# Si4825_KIT_SMT.net
KiCad netlist of a schematic drawn in EAGLE
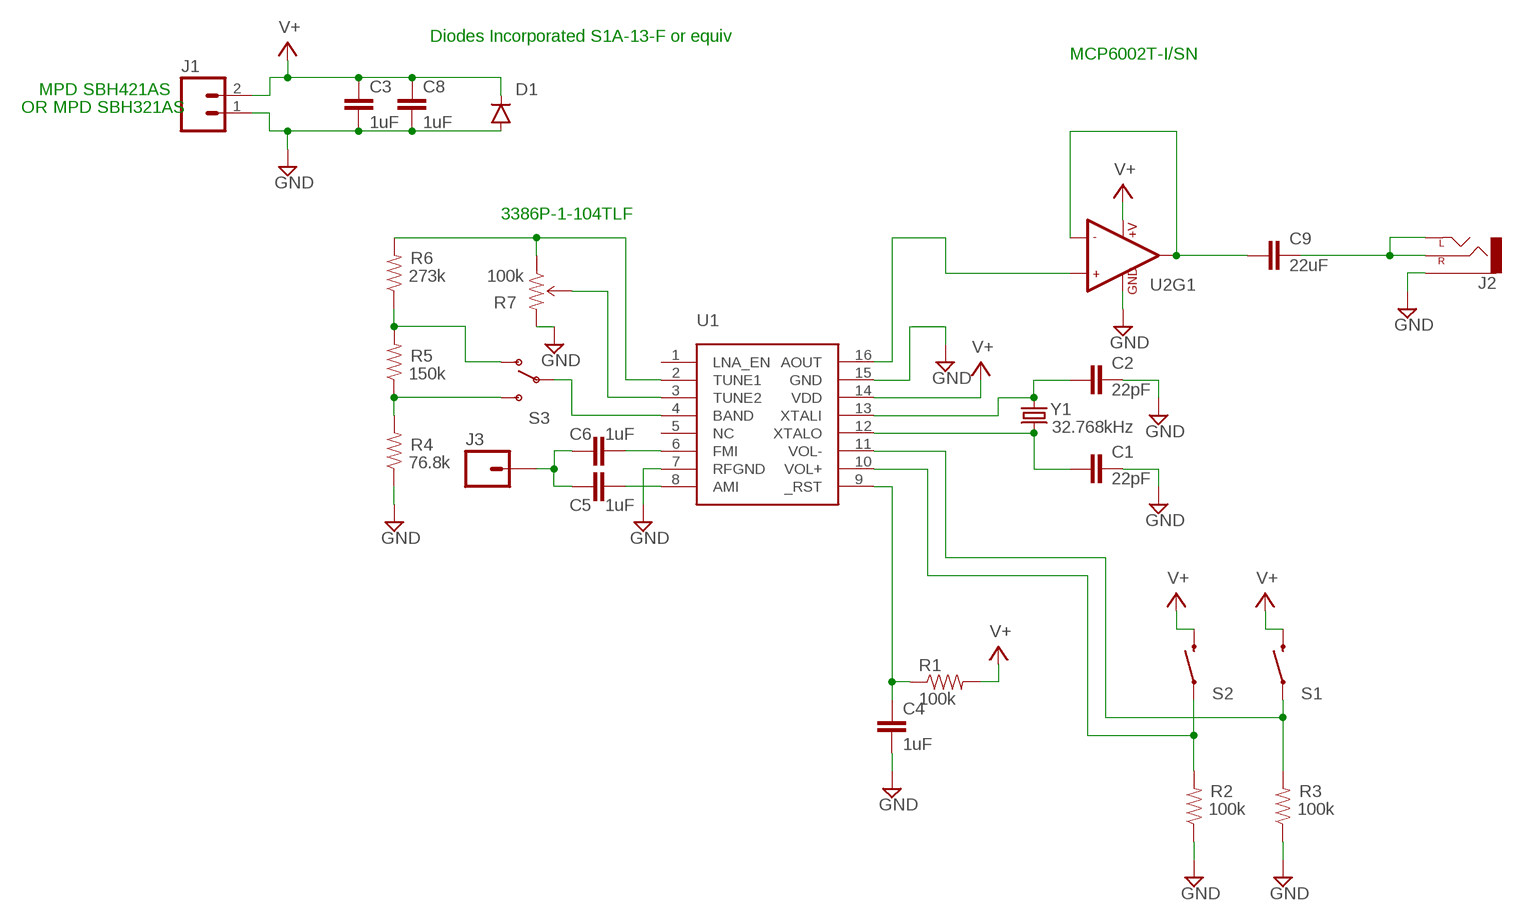
[diagram p0: schematic, sheet 1]

(export (version "E")
  (design (tool "Eeschema 10.0.6"))
  (components
    (comp (ref "C1")
      (value "22pF")
      (footprint "eagle-import:0805")
      (libsource (lib "eagle-import") (part "CAP0805"))
    )
    (comp (ref "C2")
      (value "22pF")
      (footprint "eagle-import:0805")
      (libsource (lib "eagle-import") (part "CAP0805"))
    )
    (comp (ref "C3")
      (value "1uF")
      (footprint "eagle-import:0805")
      (libsource (lib "eagle-import") (part "CAP0805"))
    )
    (comp (ref "C4")
      (value "1uF")
      (footprint "eagle-import:0805")
      (libsource (lib "eagle-import") (part "CAP0805"))
    )
    (comp (ref "C5")
      (value "1uF")
      (footprint "eagle-import:0805")
      (libsource (lib "eagle-import") (part "CAP0805"))
    )
    (comp (ref "C6")
      (value "1uF")
      (footprint "eagle-import:0805")
      (libsource (lib "eagle-import") (part "CAP0805"))
    )
    (comp (ref "C8")
      (value "1uF")
      (footprint "eagle-import:0805")
      (libsource (lib "eagle-import") (part "CAP0805"))
    )
    (comp (ref "C9")
      (value "22uF")
      (footprint "eagle-import:0805")
      (libsource (lib "eagle-import") (part "CAP0805"))
    )
    (comp (ref "D1")
      (value "DIODESMA")
      (footprint "eagle-import:SMA-DIODE")
      (libsource (lib "eagle-import") (part "DIODESMA"))
    )
    (comp (ref "J1")
      (value "M02PTH")
      (footprint "eagle-import:1X02")
      (libsource (lib "eagle-import") (part "M02PTH"))
    )
    (comp (ref "J2")
      (value "AUDIO-JACKPTH")
      (footprint "eagle-import:AUDIO-JACK")
      (libsource (lib "eagle-import") (part "AUDIO-JACKPTH"))
    )
    (comp (ref "J3")
      (value "M01PTH")
      (footprint "eagle-import:1X01")
      (libsource (lib "eagle-import") (part "M01PTH"))
    )
    (comp (ref "R1")
      (value "100k")
      (footprint "eagle-import:0805")
      (libsource (lib "eagle-import") (part "RESISTOR0805-RES"))
    )
    (comp (ref "R2")
      (value "100k")
      (footprint "eagle-import:0805")
      (libsource (lib "eagle-import") (part "RESISTOR0805-RES"))
    )
    (comp (ref "R3")
      (value "100k")
      (footprint "eagle-import:0805")
      (libsource (lib "eagle-import") (part "RESISTOR0805-RES"))
    )
    (comp (ref "R4")
      (value "76.8k")
      (footprint "eagle-import:0805")
      (libsource (lib "eagle-import") (part "RESISTOR0805-RES"))
    )
    (comp (ref "R5")
      (value "150k")
      (footprint "eagle-import:0805")
      (libsource (lib "eagle-import") (part "RESISTOR0805-RES"))
    )
    (comp (ref "R6")
      (value "273k")
      (footprint "eagle-import:0805")
      (libsource (lib "eagle-import") (part "RESISTOR0805-RES"))
    )
    (comp (ref "R7")
      (value "100k")
      (footprint "eagle-import:BOURNS_3386P")
      (libsource (lib "eagle-import") (part "BOURNS_3386P"))
    )
    (comp (ref "S1")
      (value "SWITCH-MOMENTARY-2PTH")
      (footprint "eagle-import:TACTILE-PTH")
      (libsource (lib "eagle-import") (part "SWITCH-MOMENTARY-2PTH"))
    )
    (comp (ref "S2")
      (value "SWITCH-MOMENTARY-2PTH")
      (footprint "eagle-import:TACTILE-PTH")
      (libsource (lib "eagle-import") (part "SWITCH-MOMENTARY-2PTH"))
    )
    (comp (ref "S3")
      (value "SWITCH-SPDTPTH")
      (footprint "eagle-import:SWITCH-SPDT")
      (libsource (lib "eagle-import") (part "SWITCH-SPDTPTH"))
    )
    (comp (ref "U1")
      (value "SI4825")
      (footprint "eagle-import:SO16")
      (libsource (lib "eagle-import") (part "SI4825"))
    )
    (comp (ref "U2")
      (value "LMV358SOIC")
      (footprint "eagle-import:SO08")
      (libsource (lib "eagle-import") (part "LMV358SOIC"))
    )
    (comp (ref "Y1")
      (value "32.768kHz")
      (footprint "eagle-import:TC26H")
      (libsource (lib "eagle-import") (part "CRYSTALTC26H"))
    )
  )
  (nets
    (net (code "1") (name "GND") (class "Default")
      (node (ref "C1") (pin "2") (pinfunction "2_2") (pintype "passive"))
      (node (ref "C2") (pin "2") (pinfunction "2_2") (pintype "passive"))
      (node (ref "C3") (pin "2") (pinfunction "2_2") (pintype "passive"))
      (node (ref "C4") (pin "2") (pinfunction "2_2") (pintype "passive"))
      (node (ref "C8") (pin "2") (pinfunction "2_2") (pintype "passive"))
      (node (ref "D1") (pin "A") (pinfunction "A_A") (pintype "passive"))
      (node (ref "J1") (pin "1") (pinfunction "1_1") (pintype "passive"))
      (node (ref "J2") (pin "SLEEVE") (pinfunction "SLEEVE_SLEEVE") (pintype "bidirectional"))
      (node (ref "R2") (pin "1") (pinfunction "1_1") (pintype "passive"))
      (node (ref "R3") (pin "1") (pinfunction "1_1") (pintype "passive"))
      (node (ref "R4") (pin "1") (pinfunction "1_1") (pintype "passive"))
      (node (ref "R7") (pin "P$3") (pinfunction "CW_P$3") (pintype "passive"))
      (node (ref "U1") (pin "15") (pinfunction "GND_15") (pintype "bidirectional"))
      (node (ref "U1") (pin "7") (pinfunction "RFGND_7") (pintype "bidirectional"))
      (node (ref "U2") (pin "4") (pinfunction "GND_4") (pintype "power_in"))
    )
    (net (code "2") (name "Net-(C5-Pad1)") (class "Default")
      (node (ref "C5") (pin "1") (pinfunction "1_1") (pintype "passive"))
      (node (ref "C6") (pin "1") (pinfunction "1_1") (pintype "passive"))
      (node (ref "J3") (pin "1") (pinfunction "1_1") (pintype "passive"))
    )
    (net (code "3") (name "Net-(J2-LEFT)") (class "Default")
      (node (ref "C9") (pin "2") (pinfunction "2_2") (pintype "passive"))
      (node (ref "J2") (pin "RING") (pinfunction "RIGHT_RING") (pintype "bidirectional"))
      (node (ref "J2") (pin "TIP") (pinfunction "LEFT_TIP") (pintype "bidirectional"))
    )
    (net (code "4") (name "Net-(R7-CCW)") (class "Default")
      (node (ref "R6") (pin "2") (pinfunction "2_2") (pintype "passive"))
      (node (ref "R7") (pin "P$1") (pinfunction "CCW_P$1") (pintype "passive"))
      (node (ref "U1") (pin "2") (pinfunction "TUNE1_2") (pintype "bidirectional"))
    )
    (net (code "5") (name "Net-(R7-WIPER)") (class "Default")
      (node (ref "R7") (pin "P$2") (pinfunction "WIPER_P$2") (pintype "passive"))
      (node (ref "U1") (pin "3") (pinfunction "TUNE2_3") (pintype "bidirectional"))
    )
    (net (code "6") (name "Net-(S3-O)") (class "Default")
      (node (ref "R5") (pin "2") (pinfunction "2_2") (pintype "passive"))
      (node (ref "R6") (pin "1") (pinfunction "1_1") (pintype "passive"))
      (node (ref "S3") (pin "1") (pinfunction "O_1") (pintype "passive"))
    )
    (net (code "7") (name "Net-(S3-P)") (class "Default")
      (node (ref "S3") (pin "2") (pinfunction "P_2") (pintype "passive"))
      (node (ref "U1") (pin "4") (pinfunction "BAND_4") (pintype "bidirectional"))
    )
    (net (code "8") (name "Net-(S3-S)") (class "Default")
      (node (ref "R4") (pin "2") (pinfunction "2_2") (pintype "passive"))
      (node (ref "R5") (pin "1") (pinfunction "1_1") (pintype "passive"))
      (node (ref "S3") (pin "3") (pinfunction "S_3") (pintype "passive"))
    )
    (net (code "9") (name "Net-(U1-AMI)") (class "Default")
      (node (ref "C5") (pin "2") (pinfunction "2_2") (pintype "passive"))
      (node (ref "U1") (pin "8") (pinfunction "AMI_8") (pintype "bidirectional"))
    )
    (net (code "10") (name "Net-(U1-AOUT)") (class "Default")
      (node (ref "U1") (pin "16") (pinfunction "AOUT_16") (pintype "bidirectional"))
      (node (ref "U2") (pin "3") (pinfunction "+IN1_3") (pintype "input"))
    )
    (net (code "11") (name "Net-(U1-FMI)") (class "Default")
      (node (ref "C6") (pin "2") (pinfunction "2_2") (pintype "passive"))
      (node (ref "U1") (pin "6") (pinfunction "FMI_6") (pintype "bidirectional"))
    )
    (net (code "12") (name "Net-(U1-VOL+)") (class "Default")
      (node (ref "R2") (pin "2") (pinfunction "2_2") (pintype "passive"))
      (node (ref "S2") (pin "1") (pinfunction "1_1") (pintype "passive"))
      (node (ref "U1") (pin "10") (pinfunction "VOL+_10") (pintype "bidirectional"))
    )
    (net (code "13") (name "Net-(U1-VOL-)") (class "Default")
      (node (ref "R3") (pin "2") (pinfunction "2_2") (pintype "passive"))
      (node (ref "S1") (pin "1") (pinfunction "1_1") (pintype "passive"))
      (node (ref "U1") (pin "11") (pinfunction "VOL-_11") (pintype "bidirectional"))
    )
    (net (code "14") (name "Net-(U1-XTALI)") (class "Default")
      (node (ref "C2") (pin "1") (pinfunction "1_1") (pintype "passive"))
      (node (ref "U1") (pin "13") (pinfunction "XTALI_13") (pintype "bidirectional"))
      (node (ref "Y1") (pin "1") (pinfunction "1_1") (pintype "passive"))
    )
    (net (code "15") (name "Net-(U1-XTALO)") (class "Default")
      (node (ref "C1") (pin "1") (pinfunction "1_1") (pintype "passive"))
      (node (ref "U1") (pin "12") (pinfunction "XTALO_12") (pintype "bidirectional"))
      (node (ref "Y1") (pin "2") (pinfunction "2_2") (pintype "passive"))
    )
    (net (code "16") (name "Net-(U1-_RST)") (class "Default")
      (node (ref "C4") (pin "1") (pinfunction "1_1") (pintype "passive"))
      (node (ref "R1") (pin "1") (pinfunction "1_1") (pintype "passive"))
      (node (ref "U1") (pin "9") (pinfunction "_RST_9") (pintype "bidirectional"))
    )
    (net (code "17") (name "Net-(U2A--IN1)") (class "Default")
      (node (ref "C9") (pin "1") (pinfunction "1_1") (pintype "passive"))
      (node (ref "U2") (pin "1") (pinfunction "OUT1_1") (pintype "output"))
      (node (ref "U2") (pin "2") (pinfunction "-IN1_2") (pintype "input"))
    )
    (net (code "18") (name "V+") (class "Default")
      (node (ref "C3") (pin "1") (pinfunction "1_1") (pintype "passive"))
      (node (ref "C8") (pin "1") (pinfunction "1_1") (pintype "passive"))
      (node (ref "D1") (pin "C") (pinfunction "C_C") (pintype "passive"))
      (node (ref "J1") (pin "2") (pinfunction "2_2") (pintype "passive"))
      (node (ref "R1") (pin "2") (pinfunction "2_2") (pintype "passive"))
      (node (ref "S1") (pin "3") (pinfunction "2_3") (pintype "passive"))
      (node (ref "S2") (pin "3") (pinfunction "2_3") (pintype "passive"))
      (node (ref "U1") (pin "14") (pinfunction "VDD_14") (pintype "bidirectional"))
      (node (ref "U2") (pin "8") (pinfunction "+V_8") (pintype "power_in"))
    )
    (net (code "19") (name "unconnected-(U1-LNA_EN-Pad1)") (class "Default")
      (node (ref "U1") (pin "1") (pinfunction "LNA_EN_1") (pintype "bidirectional"))
    )
    (net (code "20") (name "unconnected-(U1-NC-Pad5)") (class "Default")
      (node (ref "U1") (pin "5") (pinfunction "NC_5") (pintype "bidirectional"))
    )
  )
)
